# fancontroller.net
KiCad netlist of a schematic drawn in EAGLE
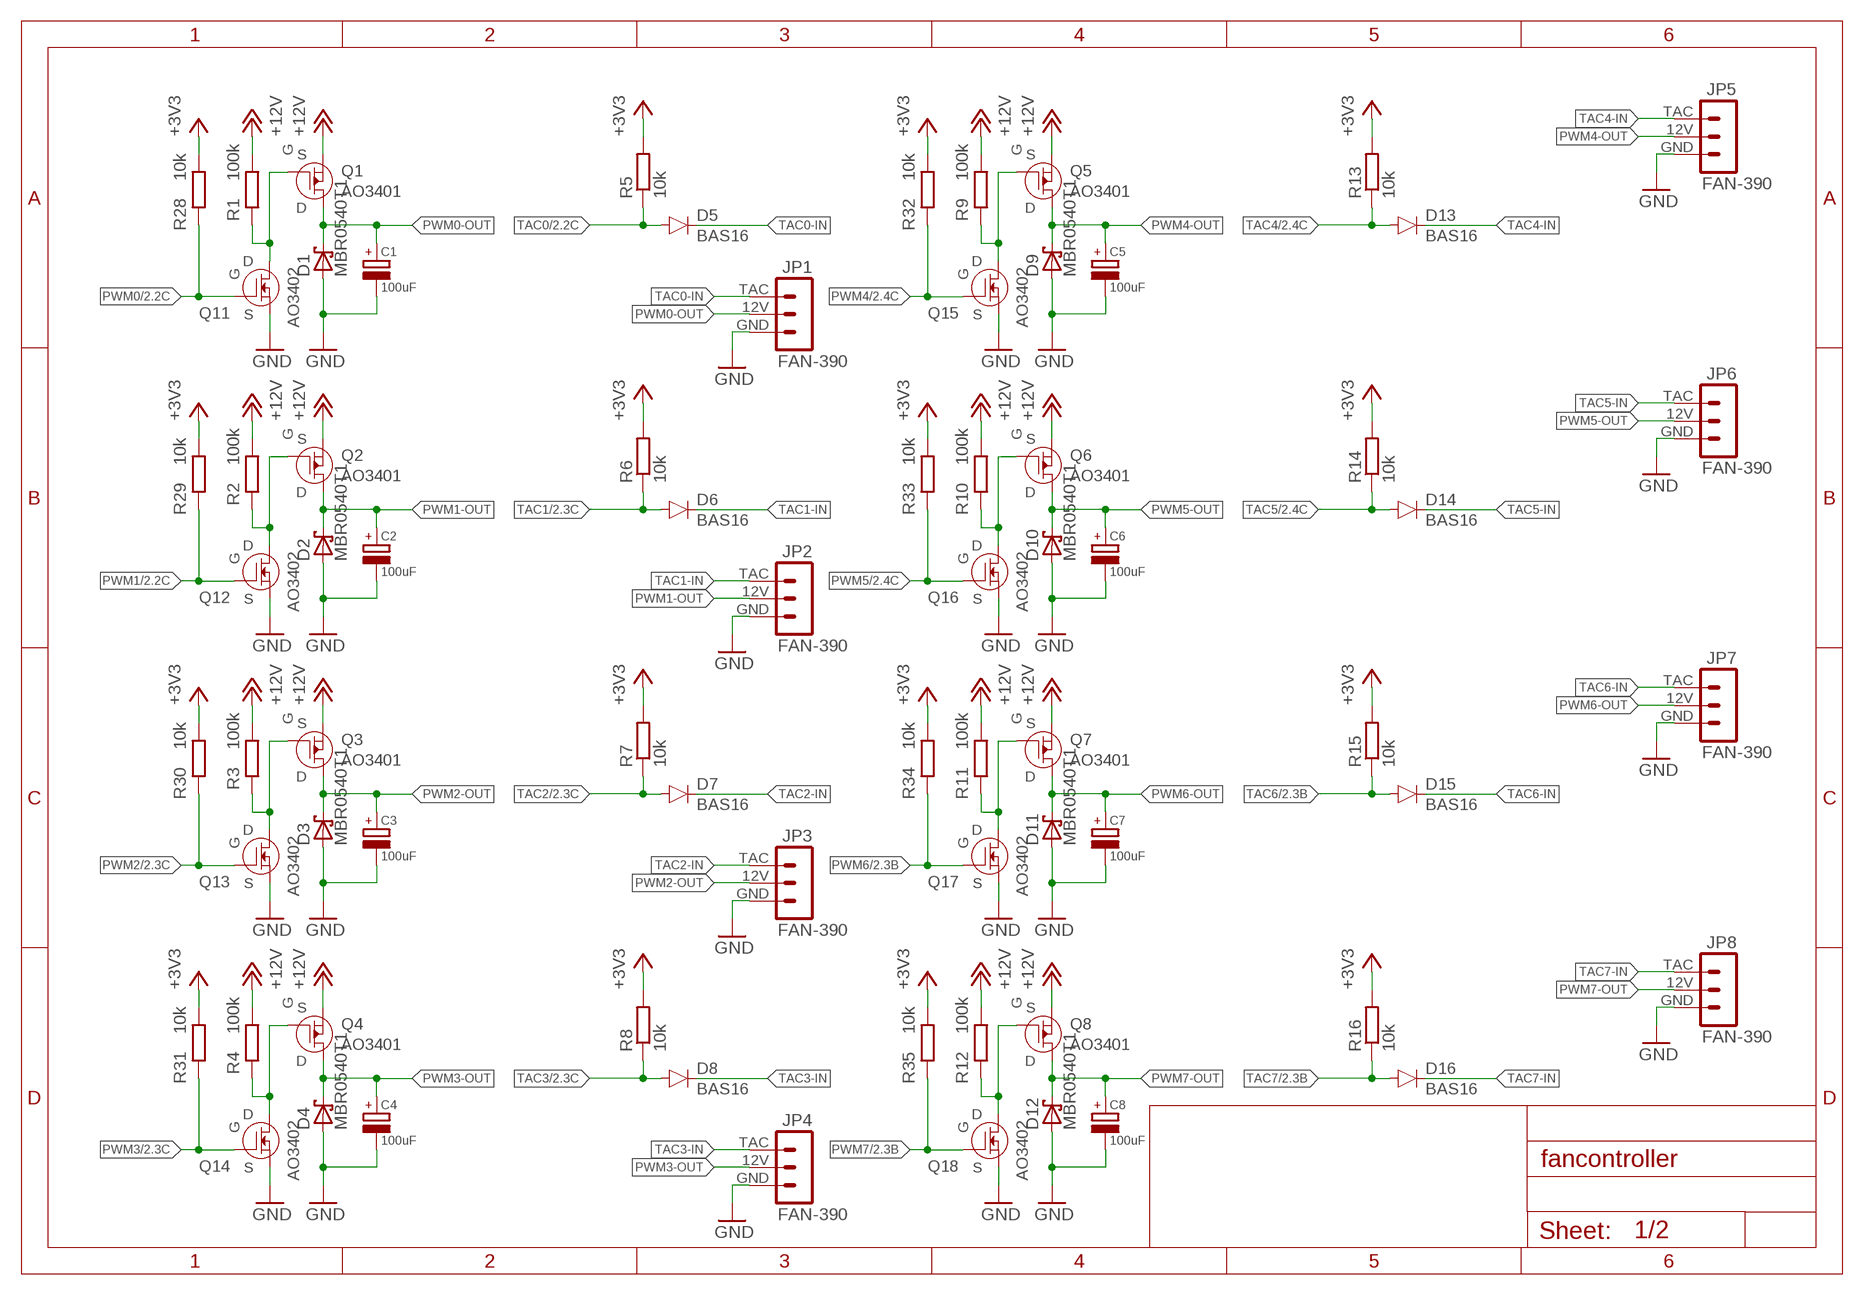
[diagram p0: schematic, sheet 1]
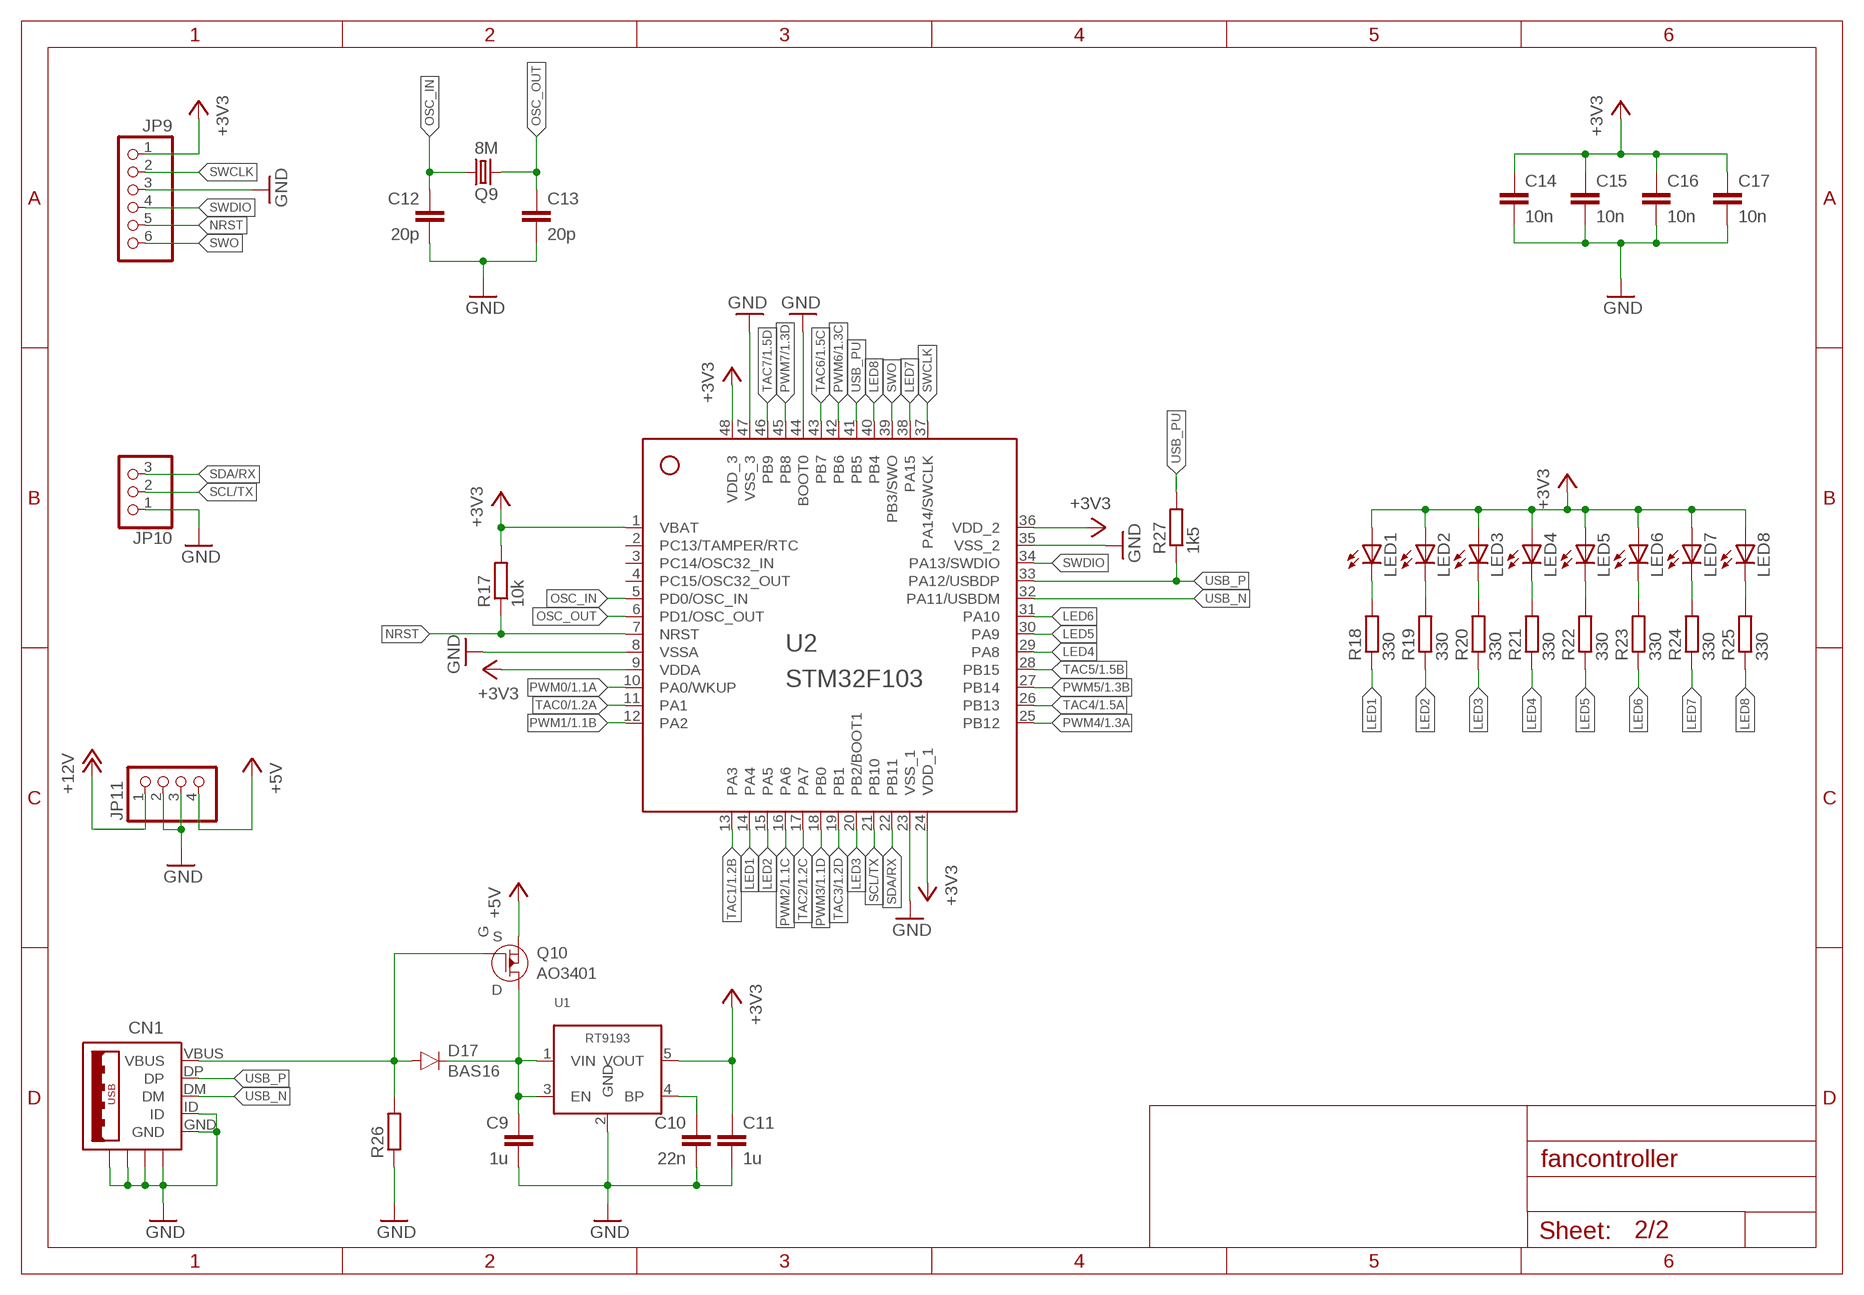
[diagram p1: schematic, sheet 2]

(export (version "E")
  (design (tool "Eeschema 10.0.6"))
  (components
    (comp (ref "C9")
      (value "1u")
      (footprint "eagle-import:0603")
      (libsource (lib "eagle-import") (part "C0603"))
    )
    (comp (ref "C10")
      (value "22n")
      (footprint "eagle-import:0603")
      (libsource (lib "eagle-import") (part "C0603"))
    )
    (comp (ref "C11")
      (value "1u")
      (footprint "eagle-import:0603")
      (libsource (lib "eagle-import") (part "C0603"))
    )
    (comp (ref "C12")
      (value "20p")
      (footprint "eagle-import:0603")
      (libsource (lib "eagle-import") (part "C0603"))
    )
    (comp (ref "C13")
      (value "20p")
      (footprint "eagle-import:0603")
      (libsource (lib "eagle-import") (part "C0603"))
    )
    (comp (ref "C14")
      (value "10n")
      (footprint "eagle-import:0603")
      (libsource (lib "eagle-import") (part "C0603"))
    )
    (comp (ref "C15")
      (value "10n")
      (footprint "eagle-import:0603")
      (libsource (lib "eagle-import") (part "C0603"))
    )
    (comp (ref "C16")
      (value "10n")
      (footprint "eagle-import:0603")
      (libsource (lib "eagle-import") (part "C0603"))
    )
    (comp (ref "C17")
      (value "10n")
      (footprint "eagle-import:0603")
      (libsource (lib "eagle-import") (part "C0603"))
    )
    (comp (ref "CN1")
      (value "USB-MICROB-2TABS")
      (footprint "eagle-import:USB-MICROB-2")
      (libsource (lib "eagle-import") (part "USB-MICROB-2TABS"))
    )
    (comp (ref "D17")
      (value "BAS16")
      (footprint "eagle-import:SOT23-3")
      (libsource (lib "eagle-import") (part "BAS16"))
    )
    (comp (ref "JP9")
      (value "PINHD-1X6")
      (footprint "eagle-import:1X06")
      (libsource (lib "eagle-import") (part "PINHD-1X6"))
    )
    (comp (ref "JP10")
      (value "PINHD-1X3/90")
      (footprint "eagle-import:1X03_90")
      (libsource (lib "eagle-import") (part "PINHD-1X3/90"))
    )
    (comp (ref "JP11")
      (value "PINHD-1X4/90")
      (footprint "eagle-import:1X04_90")
      (libsource (lib "eagle-import") (part "PINHD-1X4/90"))
    )
    (comp (ref "LED1")
      (value "LEDSML0805")
      (footprint "eagle-import:SML0805")
      (libsource (lib "eagle-import") (part "LEDSML0805"))
    )
    (comp (ref "LED2")
      (value "LEDSML0805")
      (footprint "eagle-import:SML0805")
      (libsource (lib "eagle-import") (part "LEDSML0805"))
    )
    (comp (ref "LED3")
      (value "LEDSML0805")
      (footprint "eagle-import:SML0805")
      (libsource (lib "eagle-import") (part "LEDSML0805"))
    )
    (comp (ref "LED4")
      (value "LEDSML0805")
      (footprint "eagle-import:SML0805")
      (libsource (lib "eagle-import") (part "LEDSML0805"))
    )
    (comp (ref "LED5")
      (value "LEDSML0805")
      (footprint "eagle-import:SML0805")
      (libsource (lib "eagle-import") (part "LEDSML0805"))
    )
    (comp (ref "LED6")
      (value "LEDSML0805")
      (footprint "eagle-import:SML0805")
      (libsource (lib "eagle-import") (part "LEDSML0805"))
    )
    (comp (ref "LED7")
      (value "LEDSML0805")
      (footprint "eagle-import:SML0805")
      (libsource (lib "eagle-import") (part "LEDSML0805"))
    )
    (comp (ref "LED8")
      (value "LEDSML0805")
      (footprint "eagle-import:SML0805")
      (libsource (lib "eagle-import") (part "LEDSML0805"))
    )
    (comp (ref "Q9")
      (value "8M")
      (footprint "eagle-import:HC49_S")
      (libsource (lib "eagle-import") (part "CRYSTALHC49S"))
    )
    (comp (ref "Q10")
      (value "AO3401")
      (footprint "eagle-import:SOT23-3")
      (libsource (lib "eagle-import") (part "AO3401"))
    )
    (comp (ref "R17")
      (value "10k")
      (footprint "eagle-import:R0603")
      (libsource (lib "eagle-import") (part "RR0603"))
    )
    (comp (ref "R18")
      (value "330")
      (footprint "eagle-import:R0603")
      (libsource (lib "eagle-import") (part "RR0603"))
    )
    (comp (ref "R19")
      (value "330")
      (footprint "eagle-import:R0603")
      (libsource (lib "eagle-import") (part "RR0603"))
    )
    (comp (ref "R20")
      (value "330")
      (footprint "eagle-import:R0603")
      (libsource (lib "eagle-import") (part "RR0603"))
    )
    (comp (ref "R21")
      (value "330")
      (footprint "eagle-import:R0603")
      (libsource (lib "eagle-import") (part "RR0603"))
    )
    (comp (ref "R22")
      (value "330")
      (footprint "eagle-import:R0603")
      (libsource (lib "eagle-import") (part "RR0603"))
    )
    (comp (ref "R23")
      (value "330")
      (footprint "eagle-import:R0603")
      (libsource (lib "eagle-import") (part "RR0603"))
    )
    (comp (ref "R24")
      (value "330")
      (footprint "eagle-import:R0603")
      (libsource (lib "eagle-import") (part "RR0603"))
    )
    (comp (ref "R25")
      (value "330")
      (footprint "eagle-import:R0603")
      (libsource (lib "eagle-import") (part "RR0603"))
    )
    (comp (ref "R26")
      (value "RR0603")
      (footprint "eagle-import:R0603")
      (libsource (lib "eagle-import") (part "RR0603"))
    )
    (comp (ref "R27")
      (value "1k5")
      (footprint "eagle-import:R0603")
      (libsource (lib "eagle-import") (part "RR0603"))
    )
    (comp (ref "U1")
      (value "RT9193")
      (footprint "eagle-import:SOT23-5")
      (libsource (lib "eagle-import") (part "RT9193"))
    )
    (comp (ref "U2")
      (value "STM32F103-48LQFP")
      (footprint "eagle-import:LQFP-48")
      (libsource (lib "eagle-import") (part "STM32F103-48LQFP"))
    )
    (comp (ref "C1")
      (value "100uF")
      (footprint "eagle-import:CAP-D6.3")
      (libsource (lib "eagle-import") (part "CAPACITOR"))
    )
    (comp (ref "C2")
      (value "100uF")
      (footprint "eagle-import:CAP-D6.3")
      (libsource (lib "eagle-import") (part "CAPACITOR"))
    )
    (comp (ref "C3")
      (value "100uF")
      (footprint "eagle-import:CAP-D6.3")
      (libsource (lib "eagle-import") (part "CAPACITOR"))
    )
    (comp (ref "C4")
      (value "100uF")
      (footprint "eagle-import:CAP-D6.3")
      (libsource (lib "eagle-import") (part "CAPACITOR"))
    )
    (comp (ref "C5")
      (value "100uF")
      (footprint "eagle-import:CAP-D6.3")
      (libsource (lib "eagle-import") (part "CAPACITOR"))
    )
    (comp (ref "C6")
      (value "100uF")
      (footprint "eagle-import:CAP-D6.3")
      (libsource (lib "eagle-import") (part "CAPACITOR"))
    )
    (comp (ref "C7")
      (value "100uF")
      (footprint "eagle-import:CAP-D6.3")
      (libsource (lib "eagle-import") (part "CAPACITOR"))
    )
    (comp (ref "C8")
      (value "100uF")
      (footprint "eagle-import:CAP-D6.3")
      (libsource (lib "eagle-import") (part "CAPACITOR"))
    )
    (comp (ref "D1")
      (value "MBR0540T1")
      (footprint "eagle-import:SOD123")
      (libsource (lib "eagle-import") (part "MBR0540T1"))
    )
    (comp (ref "D2")
      (value "MBR0540T1")
      (footprint "eagle-import:SOD123")
      (libsource (lib "eagle-import") (part "MBR0540T1"))
    )
    (comp (ref "D3")
      (value "MBR0540T1")
      (footprint "eagle-import:SOD123")
      (libsource (lib "eagle-import") (part "MBR0540T1"))
    )
    (comp (ref "D4")
      (value "MBR0540T1")
      (footprint "eagle-import:SOD123")
      (libsource (lib "eagle-import") (part "MBR0540T1"))
    )
    (comp (ref "D5")
      (value "BAS16")
      (footprint "eagle-import:SOT23-3")
      (libsource (lib "eagle-import") (part "BAS16"))
    )
    (comp (ref "D6")
      (value "BAS16")
      (footprint "eagle-import:SOT23-3")
      (libsource (lib "eagle-import") (part "BAS16"))
    )
    (comp (ref "D7")
      (value "BAS16")
      (footprint "eagle-import:SOT23-3")
      (libsource (lib "eagle-import") (part "BAS16"))
    )
    (comp (ref "D8")
      (value "BAS16")
      (footprint "eagle-import:SOT23-3")
      (libsource (lib "eagle-import") (part "BAS16"))
    )
    (comp (ref "D9")
      (value "MBR0540T1")
      (footprint "eagle-import:SOD123")
      (libsource (lib "eagle-import") (part "MBR0540T1"))
    )
    (comp (ref "D10")
      (value "MBR0540T1")
      (footprint "eagle-import:SOD123")
      (libsource (lib "eagle-import") (part "MBR0540T1"))
    )
    (comp (ref "D11")
      (value "MBR0540T1")
      (footprint "eagle-import:SOD123")
      (libsource (lib "eagle-import") (part "MBR0540T1"))
    )
    (comp (ref "D12")
      (value "MBR0540T1")
      (footprint "eagle-import:SOD123")
      (libsource (lib "eagle-import") (part "MBR0540T1"))
    )
    (comp (ref "D13")
      (value "BAS16")
      (footprint "eagle-import:SOT23-3")
      (libsource (lib "eagle-import") (part "BAS16"))
    )
    (comp (ref "D14")
      (value "BAS16")
      (footprint "eagle-import:SOT23-3")
      (libsource (lib "eagle-import") (part "BAS16"))
    )
    (comp (ref "D15")
      (value "BAS16")
      (footprint "eagle-import:SOT23-3")
      (libsource (lib "eagle-import") (part "BAS16"))
    )
    (comp (ref "D16")
      (value "BAS16")
      (footprint "eagle-import:SOT23-3")
      (libsource (lib "eagle-import") (part "BAS16"))
    )
    (comp (ref "JP1")
      (value "FAN-390")
      (footprint "eagle-import:FAN-3PIN_90")
      (libsource (lib "eagle-import") (part "FAN-390"))
    )
    (comp (ref "JP2")
      (value "FAN-390")
      (footprint "eagle-import:FAN-3PIN_90")
      (libsource (lib "eagle-import") (part "FAN-390"))
    )
    (comp (ref "JP3")
      (value "FAN-390")
      (footprint "eagle-import:FAN-3PIN_90")
      (libsource (lib "eagle-import") (part "FAN-390"))
    )
    (comp (ref "JP4")
      (value "FAN-390")
      (footprint "eagle-import:FAN-3PIN_90")
      (libsource (lib "eagle-import") (part "FAN-390"))
    )
    (comp (ref "JP5")
      (value "FAN-390")
      (footprint "eagle-import:FAN-3PIN_90")
      (libsource (lib "eagle-import") (part "FAN-390"))
    )
    (comp (ref "JP6")
      (value "FAN-390")
      (footprint "eagle-import:FAN-3PIN_90")
      (libsource (lib "eagle-import") (part "FAN-390"))
    )
    (comp (ref "JP7")
      (value "FAN-390")
      (footprint "eagle-import:FAN-3PIN_90")
      (libsource (lib "eagle-import") (part "FAN-390"))
    )
    (comp (ref "JP8")
      (value "FAN-390")
      (footprint "eagle-import:FAN-3PIN_90")
      (libsource (lib "eagle-import") (part "FAN-390"))
    )
    (comp (ref "Q1")
      (value "AO3401")
      (footprint "eagle-import:SOT23-3")
      (libsource (lib "eagle-import") (part "AO3401"))
    )
    (comp (ref "Q2")
      (value "AO3401")
      (footprint "eagle-import:SOT23-3")
      (libsource (lib "eagle-import") (part "AO3401"))
    )
    (comp (ref "Q3")
      (value "AO3401")
      (footprint "eagle-import:SOT23-3")
      (libsource (lib "eagle-import") (part "AO3401"))
    )
    (comp (ref "Q4")
      (value "AO3401")
      (footprint "eagle-import:SOT23-3")
      (libsource (lib "eagle-import") (part "AO3401"))
    )
    (comp (ref "Q5")
      (value "AO3401")
      (footprint "eagle-import:SOT23-3")
      (libsource (lib "eagle-import") (part "AO3401"))
    )
    (comp (ref "Q6")
      (value "AO3401")
      (footprint "eagle-import:SOT23-3")
      (libsource (lib "eagle-import") (part "AO3401"))
    )
    (comp (ref "Q7")
      (value "AO3401")
      (footprint "eagle-import:SOT23-3")
      (libsource (lib "eagle-import") (part "AO3401"))
    )
    (comp (ref "Q8")
      (value "AO3401")
      (footprint "eagle-import:SOT23-3")
      (libsource (lib "eagle-import") (part "AO3401"))
    )
    (comp (ref "Q11")
      (value "AO3402")
      (footprint "eagle-import:SOT23-3")
      (libsource (lib "eagle-import") (part "AO3402"))
    )
    (comp (ref "Q12")
      (value "AO3402")
      (footprint "eagle-import:SOT23-3")
      (libsource (lib "eagle-import") (part "AO3402"))
    )
    (comp (ref "Q13")
      (value "AO3402")
      (footprint "eagle-import:SOT23-3")
      (libsource (lib "eagle-import") (part "AO3402"))
    )
    (comp (ref "Q14")
      (value "AO3402")
      (footprint "eagle-import:SOT23-3")
      (libsource (lib "eagle-import") (part "AO3402"))
    )
    (comp (ref "Q15")
      (value "AO3402")
      (footprint "eagle-import:SOT23-3")
      (libsource (lib "eagle-import") (part "AO3402"))
    )
    (comp (ref "Q16")
      (value "AO3402")
      (footprint "eagle-import:SOT23-3")
      (libsource (lib "eagle-import") (part "AO3402"))
    )
    (comp (ref "Q17")
      (value "AO3402")
      (footprint "eagle-import:SOT23-3")
      (libsource (lib "eagle-import") (part "AO3402"))
    )
    (comp (ref "Q18")
      (value "AO3402")
      (footprint "eagle-import:SOT23-3")
      (libsource (lib "eagle-import") (part "AO3402"))
    )
    (comp (ref "R1")
      (value "100k")
      (footprint "eagle-import:R0603")
      (libsource (lib "eagle-import") (part "RR0603"))
    )
    (comp (ref "R2")
      (value "100k")
      (footprint "eagle-import:R0603")
      (libsource (lib "eagle-import") (part "RR0603"))
    )
    (comp (ref "R3")
      (value "100k")
      (footprint "eagle-import:R0603")
      (libsource (lib "eagle-import") (part "RR0603"))
    )
    (comp (ref "R4")
      (value "100k")
      (footprint "eagle-import:R0603")
      (libsource (lib "eagle-import") (part "RR0603"))
    )
    (comp (ref "R5")
      (value "10k")
      (footprint "eagle-import:R0603")
      (libsource (lib "eagle-import") (part "RR0603"))
    )
    (comp (ref "R6")
      (value "10k")
      (footprint "eagle-import:R0603")
      (libsource (lib "eagle-import") (part "RR0603"))
    )
    (comp (ref "R7")
      (value "10k")
      (footprint "eagle-import:R0603")
      (libsource (lib "eagle-import") (part "RR0603"))
    )
    (comp (ref "R8")
      (value "10k")
      (footprint "eagle-import:R0603")
      (libsource (lib "eagle-import") (part "RR0603"))
    )
    (comp (ref "R9")
      (value "100k")
      (footprint "eagle-import:R0603")
      (libsource (lib "eagle-import") (part "RR0603"))
    )
    (comp (ref "R10")
      (value "100k")
      (footprint "eagle-import:R0603")
      (libsource (lib "eagle-import") (part "RR0603"))
    )
    (comp (ref "R11")
      (value "100k")
      (footprint "eagle-import:R0603")
      (libsource (lib "eagle-import") (part "RR0603"))
    )
    (comp (ref "R12")
      (value "100k")
      (footprint "eagle-import:R0603")
      (libsource (lib "eagle-import") (part "RR0603"))
    )
    (comp (ref "R13")
      (value "10k")
      (footprint "eagle-import:R0603")
      (libsource (lib "eagle-import") (part "RR0603"))
    )
    (comp (ref "R14")
      (value "10k")
      (footprint "eagle-import:R0603")
      (libsource (lib "eagle-import") (part "RR0603"))
    )
    (comp (ref "R15")
      (value "10k")
      (footprint "eagle-import:R0603")
      (libsource (lib "eagle-import") (part "RR0603"))
    )
    (comp (ref "R16")
      (value "10k")
      (footprint "eagle-import:R0603")
      (libsource (lib "eagle-import") (part "RR0603"))
    )
    (comp (ref "R28")
      (value "10k")
      (footprint "eagle-import:R0603")
      (libsource (lib "eagle-import") (part "RR0603"))
    )
    (comp (ref "R29")
      (value "10k")
      (footprint "eagle-import:R0603")
      (libsource (lib "eagle-import") (part "RR0603"))
    )
    (comp (ref "R30")
      (value "10k")
      (footprint "eagle-import:R0603")
      (libsource (lib "eagle-import") (part "RR0603"))
    )
    (comp (ref "R31")
      (value "10k")
      (footprint "eagle-import:R0603")
      (libsource (lib "eagle-import") (part "RR0603"))
    )
    (comp (ref "R32")
      (value "10k")
      (footprint "eagle-import:R0603")
      (libsource (lib "eagle-import") (part "RR0603"))
    )
    (comp (ref "R33")
      (value "10k")
      (footprint "eagle-import:R0603")
      (libsource (lib "eagle-import") (part "RR0603"))
    )
    (comp (ref "R34")
      (value "10k")
      (footprint "eagle-import:R0603")
      (libsource (lib "eagle-import") (part "RR0603"))
    )
    (comp (ref "R35")
      (value "10k")
      (footprint "eagle-import:R0603")
      (libsource (lib "eagle-import") (part "RR0603"))
    )
  )
  (nets
    (net (code "1") (name "+3V3") (class "Default")
      (node (ref "C11") (pin "1") (pinfunction "1_1") (pintype "passive"))
      (node (ref "C14") (pin "1") (pinfunction "1_1") (pintype "passive"))
      (node (ref "C15") (pin "1") (pinfunction "1_1") (pintype "passive"))
      (node (ref "C16") (pin "1") (pinfunction "1_1") (pintype "passive"))
      (node (ref "C17") (pin "1") (pinfunction "1_1") (pintype "passive"))
      (node (ref "JP9") (pin "1") (pinfunction "1_1") (pintype "passive"))
      (node (ref "LED1") (pin "A") (pinfunction "A_A") (pintype "passive"))
      (node (ref "LED2") (pin "A") (pinfunction "A_A") (pintype "passive"))
      (node (ref "LED3") (pin "A") (pinfunction "A_A") (pintype "passive"))
      (node (ref "LED4") (pin "A") (pinfunction "A_A") (pintype "passive"))
      (node (ref "LED5") (pin "A") (pinfunction "A_A") (pintype "passive"))
      (node (ref "LED6") (pin "A") (pinfunction "A_A") (pintype "passive"))
      (node (ref "LED7") (pin "A") (pinfunction "A_A") (pintype "passive"))
      (node (ref "LED8") (pin "A") (pinfunction "A_A") (pintype "passive"))
      (node (ref "R13") (pin "2") (pinfunction "2_2") (pintype "passive"))
      (node (ref "R14") (pin "2") (pinfunction "2_2") (pintype "passive"))
      (node (ref "R15") (pin "2") (pinfunction "2_2") (pintype "passive"))
      (node (ref "R16") (pin "2") (pinfunction "2_2") (pintype "passive"))
      (node (ref "R17") (pin "2") (pinfunction "2_2") (pintype "passive"))
      (node (ref "R28") (pin "2") (pinfunction "2_2") (pintype "passive"))
      (node (ref "R29") (pin "2") (pinfunction "2_2") (pintype "passive"))
      (node (ref "R30") (pin "2") (pinfunction "2_2") (pintype "passive"))
      (node (ref "R31") (pin "2") (pinfunction "2_2") (pintype "passive"))
      (node (ref "R32") (pin "2") (pinfunction "2_2") (pintype "passive"))
      (node (ref "R33") (pin "2") (pinfunction "2_2") (pintype "passive"))
      (node (ref "R34") (pin "2") (pinfunction "2_2") (pintype "passive"))
      (node (ref "R35") (pin "2") (pinfunction "2_2") (pintype "passive"))
      (node (ref "R5") (pin "2") (pinfunction "2_2") (pintype "passive"))
      (node (ref "R6") (pin "2") (pinfunction "2_2") (pintype "passive"))
      (node (ref "R7") (pin "2") (pinfunction "2_2") (pintype "passive"))
      (node (ref "R8") (pin "2") (pinfunction "2_2") (pintype "passive"))
      (node (ref "U1") (pin "5") (pinfunction "VOUT_5") (pintype "bidirectional"))
      (node (ref "U2") (pin "1") (pinfunction "VBAT_1") (pintype "bidirectional"))
      (node (ref "U2") (pin "24") (pinfunction "VDD_1_24") (pintype "bidirectional"))
      (node (ref "U2") (pin "36") (pinfunction "VDD_2_36") (pintype "bidirectional"))
      (node (ref "U2") (pin "48") (pinfunction "VDD_3_48") (pintype "bidirectional"))
      (node (ref "U2") (pin "9") (pinfunction "VDDA_9") (pintype "bidirectional"))
    )
    (net (code "2") (name "+5V") (class "Default")
      (node (ref "JP11") (pin "4") (pinfunction "4_4") (pintype "passive"))
      (node (ref "Q10") (pin "2") (pinfunction "S_2") (pintype "bidirectional"))
    )
    (net (code "3") (name "+12V") (class "Default")
      (node (ref "JP11") (pin "1") (pinfunction "1_1") (pintype "passive"))
      (node (ref "Q1") (pin "2") (pinfunction "S_2") (pintype "bidirectional"))
      (node (ref "Q2") (pin "2") (pinfunction "S_2") (pintype "bidirectional"))
      (node (ref "Q3") (pin "2") (pinfunction "S_2") (pintype "bidirectional"))
      (node (ref "Q4") (pin "2") (pinfunction "S_2") (pintype "bidirectional"))
      (node (ref "Q5") (pin "2") (pinfunction "S_2") (pintype "bidirectional"))
      (node (ref "Q6") (pin "2") (pinfunction "S_2") (pintype "bidirectional"))
      (node (ref "Q7") (pin "2") (pinfunction "S_2") (pintype "bidirectional"))
      (node (ref "Q8") (pin "2") (pinfunction "S_2") (pintype "bidirectional"))
      (node (ref "R1") (pin "2") (pinfunction "2_2") (pintype "passive"))
      (node (ref "R10") (pin "2") (pinfunction "2_2") (pintype "passive"))
      (node (ref "R11") (pin "2") (pinfunction "2_2") (pintype "passive"))
      (node (ref "R12") (pin "2") (pinfunction "2_2") (pintype "passive"))
      (node (ref "R2") (pin "2") (pinfunction "2_2") (pintype "passive"))
      (node (ref "R3") (pin "2") (pinfunction "2_2") (pintype "passive"))
      (node (ref "R4") (pin "2") (pinfunction "2_2") (pintype "passive"))
      (node (ref "R9") (pin "2") (pinfunction "2_2") (pintype "passive"))
    )
    (net (code "4") (name "GND") (class "Default")
      (node (ref "C1") (pin "N") (pinfunction "NEG_N") (pintype "passive"))
      (node (ref "C10") (pin "2") (pinfunction "2_2") (pintype "passive"))
      (node (ref "C11") (pin "2") (pinfunction "2_2") (pintype "passive"))
      (node (ref "C12") (pin "2") (pinfunction "2_2") (pintype "passive"))
      (node (ref "C13") (pin "2") (pinfunction "2_2") (pintype "passive"))
      (node (ref "C14") (pin "2") (pinfunction "2_2") (pintype "passive"))
      (node (ref "C15") (pin "2") (pinfunction "2_2") (pintype "passive"))
      (node (ref "C16") (pin "2") (pinfunction "2_2") (pintype "passive"))
      (node (ref "C17") (pin "2") (pinfunction "2_2") (pintype "passive"))
      (node (ref "C2") (pin "N") (pinfunction "NEG_N") (pintype "passive"))
      (node (ref "C3") (pin "N") (pinfunction "NEG_N") (pintype "passive"))
      (node (ref "C4") (pin "N") (pinfunction "NEG_N") (pintype "passive"))
      (node (ref "C5") (pin "N") (pinfunction "NEG_N") (pintype "passive"))
      (node (ref "C6") (pin "N") (pinfunction "NEG_N") (pintype "passive"))
      (node (ref "C7") (pin "N") (pinfunction "NEG_N") (pintype "passive"))
      (node (ref "C8") (pin "N") (pinfunction "NEG_N") (pintype "passive"))
      (node (ref "C9") (pin "2") (pinfunction "2_2") (pintype "passive"))
      (node (ref "CN1") (pin "GND") (pinfunction "GND_GND") (pintype "passive"))
      (node (ref "CN1") (pin "GND@1") (pinfunction "GND_GND@1") (pintype "power_in"))
      (node (ref "CN1") (pin "GND@2") (pinfunction "GND_GND@2") (pintype "power_in"))
      (node (ref "CN1") (pin "GND@3") (pinfunction "GND_GND@3") (pintype "power_in"))
      (node (ref "CN1") (pin "GND@4") (pinfunction "GND_GND@4") (pintype "power_in"))
      (node (ref "CN1") (pin "ID") (pinfunction "ID_ID") (pintype "passive"))
      (node (ref "D1") (pin "A") (pinfunction "A_A") (pintype "passive"))
      (node (ref "D10") (pin "A") (pinfunction "A_A") (pintype "passive"))
      (node (ref "D11") (pin "A") (pinfunction "A_A") (pintype "passive"))
      (node (ref "D12") (pin "A") (pinfunction "A_A") (pintype "passive"))
      (node (ref "D2") (pin "A") (pinfunction "A_A") (pintype "passive"))
      (node (ref "D3") (pin "A") (pinfunction "A_A") (pintype "passive"))
      (node (ref "D4") (pin "A") (pinfunction "A_A") (pintype "passive"))
      (node (ref "D9") (pin "A") (pinfunction "A_A") (pintype "passive"))
      (node (ref "JP1") (pin "GND") (pinfunction "1_GND") (pintype "passive"))
      (node (ref "JP10") (pin "1") (pinfunction "1_1") (pintype "passive"))
      (node (ref "JP11") (pin "2") (pinfunction "2_2") (pintype "passive"))
      (node (ref "JP11") (pin "3") (pinfunction "3_3") (pintype "passive"))
      (node (ref "JP2") (pin "GND") (pinfunction "1_GND") (pintype "passive"))
      (node (ref "JP3") (pin "GND") (pinfunction "1_GND") (pintype "passive"))
      (node (ref "JP4") (pin "GND") (pinfunction "1_GND") (pintype "passive"))
      (node (ref "JP5") (pin "GND") (pinfunction "1_GND") (pintype "passive"))
      (node (ref "JP6") (pin "GND") (pinfunction "1_GND") (pintype "passive"))
      (node (ref "JP7") (pin "GND") (pinfunction "1_GND") (pintype "passive"))
      (node (ref "JP8") (pin "GND") (pinfunction "1_GND") (pintype "passive"))
      (node (ref "JP9") (pin "3") (pinfunction "3_3") (pintype "passive"))
      (node (ref "Q11") (pin "2") (pinfunction "S_2") (pintype "bidirectional"))
      (node (ref "Q12") (pin "2") (pinfunction "S_2") (pintype "bidirectional"))
      (node (ref "Q13") (pin "2") (pinfunction "S_2") (pintype "bidirectional"))
      (node (ref "Q14") (pin "2") (pinfunction "S_2") (pintype "bidirectional"))
      (node (ref "Q15") (pin "2") (pinfunction "S_2") (pintype "bidirectional"))
      (node (ref "Q16") (pin "2") (pinfunction "S_2") (pintype "bidirectional"))
      (node (ref "Q17") (pin "2") (pinfunction "S_2") (pintype "bidirectional"))
      (node (ref "Q18") (pin "2") (pinfunction "S_2") (pintype "bidirectional"))
      (node (ref "R26") (pin "1") (pinfunction "1_1") (pintype "passive"))
      (node (ref "U1") (pin "2") (pinfunction "GND_2") (pintype "bidirectional"))
      (node (ref "U2") (pin "23") (pinfunction "VSS_1_23") (pintype "bidirectional"))
      (node (ref "U2") (pin "35") (pinfunction "VSS_2_35") (pintype "bidirectional"))
      (node (ref "U2") (pin "44") (pinfunction "BOOT0_44") (pintype "bidirectional"))
      (node (ref "U2") (pin "47") (pinfunction "VSS_3_47") (pintype "bidirectional"))
      (node (ref "U2") (pin "8") (pinfunction "VSSA_8") (pintype "bidirectional"))
    )
    (net (code "5") (name "LED1") (class "Default")
      (node (ref "R18") (pin "1") (pinfunction "1_1") (pintype "passive"))
      (node (ref "U2") (pin "14") (pinfunction "PA4_14") (pintype "bidirectional"))
    )
    (net (code "6") (name "LED2") (class "Default")
      (node (ref "R19") (pin "1") (pinfunction "1_1") (pintype "passive"))
      (node (ref "U2") (pin "15") (pinfunction "PA5_15") (pintype "bidirectional"))
    )
    (net (code "7") (name "LED3") (class "Default")
      (node (ref "R20") (pin "1") (pinfunction "1_1") (pintype "passive"))
      (node (ref "U2") (pin "20") (pinfunction "PB2/BOOT1_20") (pintype "bidirectional"))
    )
    (net (code "8") (name "LED4") (class "Default")
      (node (ref "R21") (pin "1") (pinfunction "1_1") (pintype "passive"))
      (node (ref "U2") (pin "29") (pinfunction "PA8_29") (pintype "bidirectional"))
    )
    (net (code "9") (name "LED5") (class "Default")
      (node (ref "R22") (pin "1") (pinfunction "1_1") (pintype "passive"))
      (node (ref "U2") (pin "30") (pinfunction "PA9_30") (pintype "bidirectional"))
    )
    (net (code "10") (name "LED6") (class "Default")
      (node (ref "R23") (pin "1") (pinfunction "1_1") (pintype "passive"))
      (node (ref "U2") (pin "31") (pinfunction "PA10_31") (pintype "bidirectional"))
    )
    (net (code "11") (name "LED7") (class "Default")
      (node (ref "R24") (pin "1") (pinfunction "1_1") (pintype "passive"))
      (node (ref "U2") (pin "38") (pinfunction "PA15_38") (pintype "bidirectional"))
    )
    (net (code "12") (name "LED8") (class "Default")
      (node (ref "R25") (pin "1") (pinfunction "1_1") (pintype "passive"))
      (node (ref "U2") (pin "40") (pinfunction "PB4_40") (pintype "bidirectional"))
    )
    (net (code "13") (name "NRST") (class "Default")
      (node (ref "JP9") (pin "5") (pinfunction "5_5") (pintype "passive"))
      (node (ref "R17") (pin "1") (pinfunction "1_1") (pintype "passive"))
      (node (ref "U2") (pin "7") (pinfunction "NRST_7") (pintype "bidirectional"))
    )
    (net (code "14") (name "Net-(D17-A)") (class "Default")
      (node (ref "CN1") (pin "VBUS") (pinfunction "VBUS_VBUS") (pintype "passive"))
      (node (ref "D17") (pin "1") (pinfunction "A_1") (pintype "bidirectional"))
      (node (ref "Q10") (pin "1") (pinfunction "G_1") (pintype "bidirectional"))
      (node (ref "R26") (pin "2") (pinfunction "2_2") (pintype "passive"))
    )
    (net (code "15") (name "Net-(D17-C)") (class "Default")
      (node (ref "C9") (pin "1") (pinfunction "1_1") (pintype "passive"))
      (node (ref "D17") (pin "3") (pinfunction "C_3") (pintype "bidirectional"))
      (node (ref "Q10") (pin "3") (pinfunction "D_3") (pintype "bidirectional"))
      (node (ref "U1") (pin "1") (pinfunction "VIN_1") (pintype "bidirectional"))
      (node (ref "U1") (pin "3") (pinfunction "EN_3") (pintype "bidirectional"))
    )
    (net (code "16") (name "Net-(LED1-PadC)") (class "Default")
      (node (ref "LED1") (pin "C") (pinfunction "C_C") (pintype "passive"))
      (node (ref "R18") (pin "2") (pinfunction "2_2") (pintype "passive"))
    )
    (net (code "17") (name "Net-(LED2-PadC)") (class "Default")
      (node (ref "LED2") (pin "C") (pinfunction "C_C") (pintype "passive"))
      (node (ref "R19") (pin "2") (pinfunction "2_2") (pintype "passive"))
    )
    (net (code "18") (name "Net-(LED3-PadC)") (class "Default")
      (node (ref "LED3") (pin "C") (pinfunction "C_C") (pintype "passive"))
      (node (ref "R20") (pin "2") (pinfunction "2_2") (pintype "passive"))
    )
    (net (code "19") (name "Net-(LED4-PadC)") (class "Default")
      (node (ref "LED4") (pin "C") (pinfunction "C_C") (pintype "passive"))
      (node (ref "R21") (pin "2") (pinfunction "2_2") (pintype "passive"))
    )
    (net (code "20") (name "Net-(LED5-PadC)") (class "Default")
      (node (ref "LED5") (pin "C") (pinfunction "C_C") (pintype "passive"))
      (node (ref "R22") (pin "2") (pinfunction "2_2") (pintype "passive"))
    )
    (net (code "21") (name "Net-(LED6-PadC)") (class "Default")
      (node (ref "LED6") (pin "C") (pinfunction "C_C") (pintype "passive"))
      (node (ref "R23") (pin "2") (pinfunction "2_2") (pintype "passive"))
    )
    (net (code "22") (name "Net-(LED7-PadC)") (class "Default")
      (node (ref "LED7") (pin "C") (pinfunction "C_C") (pintype "passive"))
      (node (ref "R24") (pin "2") (pinfunction "2_2") (pintype "passive"))
    )
    (net (code "23") (name "Net-(LED8-PadC)") (class "Default")
      (node (ref "LED8") (pin "C") (pinfunction "C_C") (pintype "passive"))
      (node (ref "R25") (pin "2") (pinfunction "2_2") (pintype "passive"))
    )
    (net (code "24") (name "Net-(Q1-G)") (class "Default")
      (node (ref "Q1") (pin "1") (pinfunction "G_1") (pintype "bidirectional"))
      (node (ref "Q11") (pin "3") (pinfunction "D_3") (pintype "bidirectional"))
      (node (ref "R1") (pin "1") (pinfunction "1_1") (pintype "passive"))
    )
    (net (code "25") (name "Net-(Q12-D)") (class "Default")
      (node (ref "Q12") (pin "3") (pinfunction "D_3") (pintype "bidirectional"))
      (node (ref "Q2") (pin "1") (pinfunction "G_1") (pintype "bidirectional"))
      (node (ref "R2") (pin "1") (pinfunction "1_1") (pintype "passive"))
    )
    (net (code "26") (name "Net-(Q13-D)") (class "Default")
      (node (ref "Q13") (pin "3") (pinfunction "D_3") (pintype "bidirectional"))
      (node (ref "Q3") (pin "1") (pinfunction "G_1") (pintype "bidirectional"))
      (node (ref "R3") (pin "1") (pinfunction "1_1") (pintype "passive"))
    )
    (net (code "27") (name "Net-(Q14-D)") (class "Default")
      (node (ref "Q14") (pin "3") (pinfunction "D_3") (pintype "bidirectional"))
      (node (ref "Q4") (pin "1") (pinfunction "G_1") (pintype "bidirectional"))
      (node (ref "R4") (pin "1") (pinfunction "1_1") (pintype "passive"))
    )
    (net (code "28") (name "Net-(Q15-D)") (class "Default")
      (node (ref "Q15") (pin "3") (pinfunction "D_3") (pintype "bidirectional"))
      (node (ref "Q5") (pin "1") (pinfunction "G_1") (pintype "bidirectional"))
      (node (ref "R9") (pin "1") (pinfunction "1_1") (pintype "passive"))
    )
    (net (code "29") (name "Net-(Q16-D)") (class "Default")
      (node (ref "Q16") (pin "3") (pinfunction "D_3") (pintype "bidirectional"))
      (node (ref "Q6") (pin "1") (pinfunction "G_1") (pintype "bidirectional"))
      (node (ref "R10") (pin "1") (pinfunction "1_1") (pintype "passive"))
    )
    (net (code "30") (name "Net-(Q17-D)") (class "Default")
      (node (ref "Q17") (pin "3") (pinfunction "D_3") (pintype "bidirectional"))
      (node (ref "Q7") (pin "1") (pinfunction "G_1") (pintype "bidirectional"))
      (node (ref "R11") (pin "1") (pinfunction "1_1") (pintype "passive"))
    )
    (net (code "31") (name "Net-(Q18-D)") (class "Default")
      (node (ref "Q18") (pin "3") (pinfunction "D_3") (pintype "bidirectional"))
      (node (ref "Q8") (pin "1") (pinfunction "G_1") (pintype "bidirectional"))
      (node (ref "R12") (pin "1") (pinfunction "1_1") (pintype "passive"))
    )
    (net (code "32") (name "Net-(U1-BP)") (class "Default")
      (node (ref "C10") (pin "1") (pinfunction "1_1") (pintype "passive"))
      (node (ref "U1") (pin "4") (pinfunction "BP_4") (pintype "bidirectional"))
    )
    (net (code "33") (name "OSC_IN") (class "Default")
      (node (ref "C12") (pin "1") (pinfunction "1_1") (pintype "passive"))
      (node (ref "Q9") (pin "1") (pinfunction "1_1") (pintype "passive"))
      (node (ref "U2") (pin "5") (pinfunction "PD0/OSC_IN_5") (pintype "bidirectional"))
    )
    (net (code "34") (name "OSC_OUT") (class "Default")
      (node (ref "C13") (pin "1") (pinfunction "1_1") (pintype "passive"))
      (node (ref "Q9") (pin "2") (pinfunction "2_2") (pintype "passive"))
      (node (ref "U2") (pin "6") (pinfunction "PD1/OSC_OUT_6") (pintype "bidirectional"))
    )
    (net (code "35") (name "PWM0") (class "Default")
      (node (ref "Q11") (pin "1") (pinfunction "G_1") (pintype "bidirectional"))
      (node (ref "R28") (pin "1") (pinfunction "1_1") (pintype "passive"))
      (node (ref "U2") (pin "10") (pinfunction "PA0/WKUP_10") (pintype "bidirectional"))
    )
    (net (code "36") (name "PWM0-OUT") (class "Default")
      (node (ref "C1") (pin "P") (pinfunction "POS_P") (pintype "passive"))
      (node (ref "D1") (pin "C") (pinfunction "C_C") (pintype "passive"))
      (node (ref "JP1") (pin "12V") (pinfunction "2_12V") (pintype "passive"))
      (node (ref "Q1") (pin "3") (pinfunction "D_3") (pintype "bidirectional"))
    )
    (net (code "37") (name "PWM1") (class "Default")
      (node (ref "Q12") (pin "1") (pinfunction "G_1") (pintype "bidirectional"))
      (node (ref "R29") (pin "1") (pinfunction "1_1") (pintype "passive"))
      (node (ref "U2") (pin "12") (pinfunction "PA2_12") (pintype "bidirectional"))
    )
    (net (code "38") (name "PWM1-OUT") (class "Default")
      (node (ref "C2") (pin "P") (pinfunction "POS_P") (pintype "passive"))
      (node (ref "D2") (pin "C") (pinfunction "C_C") (pintype "passive"))
      (node (ref "JP2") (pin "12V") (pinfunction "2_12V") (pintype "passive"))
      (node (ref "Q2") (pin "3") (pinfunction "D_3") (pintype "bidirectional"))
    )
    (net (code "39") (name "PWM2") (class "Default")
      (node (ref "Q13") (pin "1") (pinfunction "G_1") (pintype "bidirectional"))
      (node (ref "R30") (pin "1") (pinfunction "1_1") (pintype "passive"))
      (node (ref "U2") (pin "16") (pinfunction "PA6_16") (pintype "bidirectional"))
    )
    (net (code "40") (name "PWM2-OUT") (class "Default")
      (node (ref "C3") (pin "P") (pinfunction "POS_P") (pintype "passive"))
      (node (ref "D3") (pin "C") (pinfunction "C_C") (pintype "passive"))
      (node (ref "JP3") (pin "12V") (pinfunction "2_12V") (pintype "passive"))
      (node (ref "Q3") (pin "3") (pinfunction "D_3") (pintype "bidirectional"))
    )
    (net (code "41") (name "PWM3") (class "Default")
      (node (ref "Q14") (pin "1") (pinfunction "G_1") (pintype "bidirectional"))
      (node (ref "R31") (pin "1") (pinfunction "1_1") (pintype "passive"))
      (node (ref "U2") (pin "18") (pinfunction "PB0_18") (pintype "bidirectional"))
    )
    (net (code "42") (name "PWM3-OUT") (class "Default")
      (node (ref "C4") (pin "P") (pinfunction "POS_P") (pintype "passive"))
      (node (ref "D4") (pin "C") (pinfunction "C_C") (pintype "passive"))
      (node (ref "JP4") (pin "12V") (pinfunction "2_12V") (pintype "passive"))
      (node (ref "Q4") (pin "3") (pinfunction "D_3") (pintype "bidirectional"))
    )
    (net (code "43") (name "PWM4") (class "Default")
      (node (ref "Q15") (pin "1") (pinfunction "G_1") (pintype "bidirectional"))
      (node (ref "R32") (pin "1") (pinfunction "1_1") (pintype "passive"))
      (node (ref "U2") (pin "25") (pinfunction "PB12_25") (pintype "bidirectional"))
    )
    (net (code "44") (name "PWM4-OUT") (class "Default")
      (node (ref "C5") (pin "P") (pinfunction "POS_P") (pintype "passive"))
      (node (ref "D9") (pin "C") (pinfunction "C_C") (pintype "passive"))
      (node (ref "JP5") (pin "12V") (pinfunction "2_12V") (pintype "passive"))
      (node (ref "Q5") (pin "3") (pinfunction "D_3") (pintype "bidirectional"))
    )
    (net (code "45") (name "PWM5") (class "Default")
      (node (ref "Q16") (pin "1") (pinfunction "G_1") (pintype "bidirectional"))
      (node (ref "R33") (pin "1") (pinfunction "1_1") (pintype "passive"))
      (node (ref "U2") (pin "27") (pinfunction "PB14_27") (pintype "bidirectional"))
    )
    (net (code "46") (name "PWM5-OUT") (class "Default")
      (node (ref "C6") (pin "P") (pinfunction "POS_P") (pintype "passive"))
      (node (ref "D10") (pin "C") (pinfunction "C_C") (pintype "passive"))
      (node (ref "JP6") (pin "12V") (pinfunction "2_12V") (pintype "passive"))
      (node (ref "Q6") (pin "3") (pinfunction "D_3") (pintype "bidirectional"))
    )
    (net (code "47") (name "PWM6") (class "Default")
      (node (ref "Q17") (pin "1") (pinfunction "G_1") (pintype "bidirectional"))
      (node (ref "R34") (pin "1") (pinfunction "1_1") (pintype "passive"))
      (node (ref "U2") (pin "42") (pinfunction "PB6_42") (pintype "bidirectional"))
    )
    (net (code "48") (name "PWM6-OUT") (class "Default")
      (node (ref "C7") (pin "P") (pinfunction "POS_P") (pintype "passive"))
      (node (ref "D11") (pin "C") (pinfunction "C_C") (pintype "passive"))
      (node (ref "JP7") (pin "12V") (pinfunction "2_12V") (pintype "passive"))
      (node (ref "Q7") (pin "3") (pinfunction "D_3") (pintype "bidirectional"))
    )
    (net (code "49") (name "PWM7") (class "Default")
      (node (ref "Q18") (pin "1") (pinfunction "G_1") (pintype "bidirectional"))
      (node (ref "R35") (pin "1") (pinfunction "1_1") (pintype "passive"))
      (node (ref "U2") (pin "45") (pinfunction "PB8_45") (pintype "bidirectional"))
    )
    (net (code "50") (name "PWM7-OUT") (class "Default")
      (node (ref "C8") (pin "P") (pinfunction "POS_P") (pintype "passive"))
      (node (ref "D12") (pin "C") (pinfunction "C_C") (pintype "passive"))
      (node (ref "JP8") (pin "12V") (pinfunction "2_12V") (pintype "passive"))
      (node (ref "Q8") (pin "3") (pinfunction "D_3") (pintype "bidirectional"))
    )
    (net (code "51") (name "SCL{slash}TX") (class "Default")
      (node (ref "JP10") (pin "2") (pinfunction "2_2") (pintype "passive"))
      (node (ref "U2") (pin "21") (pinfunction "PB10_21") (pintype "bidirectional"))
    )
    (net (code "52") (name "SDA{slash}RX") (class "Default")
      (node (ref "JP10") (pin "3") (pinfunction "3_3") (pintype "passive"))
      (node (ref "U2") (pin "22") (pinfunction "PB11_22") (pintype "bidirectional"))
    )
    (net (code "53") (name "SWCLK") (class "Default")
      (node (ref "JP9") (pin "2") (pinfunction "2_2") (pintype "passive"))
      (node (ref "U2") (pin "37") (pinfunction "PA14/SWCLK_37") (pintype "bidirectional"))
    )
    (net (code "54") (name "SWDIO") (class "Default")
      (node (ref "JP9") (pin "4") (pinfunction "4_4") (pintype "passive"))
      (node (ref "U2") (pin "34") (pinfunction "PA13/SWDIO_34") (pintype "bidirectional"))
    )
    (net (code "55") (name "SWO") (class "Default")
      (node (ref "JP9") (pin "6") (pinfunction "6_6") (pintype "passive"))
      (node (ref "U2") (pin "39") (pinfunction "PB3/SWO_39") (pintype "bidirectional"))
    )
    (net (code "56") (name "TAC0") (class "Default")
      (node (ref "D5") (pin "1") (pinfunction "A_1") (pintype "bidirectional"))
      (node (ref "R5") (pin "1") (pinfunction "1_1") (pintype "passive"))
      (node (ref "U2") (pin "11") (pinfunction "PA1_11") (pintype "bidirectional"))
    )
    (net (code "57") (name "TAC0-IN") (class "Default")
      (node (ref "D5") (pin "3") (pinfunction "C_3") (pintype "bidirectional"))
      (node (ref "JP1") (pin "TAC") (pinfunction "3_TAC") (pintype "passive"))
    )
    (net (code "58") (name "TAC1") (class "Default")
      (node (ref "D6") (pin "1") (pinfunction "A_1") (pintype "bidirectional"))
      (node (ref "R6") (pin "1") (pinfunction "1_1") (pintype "passive"))
      (node (ref "U2") (pin "13") (pinfunction "PA3_13") (pintype "bidirectional"))
    )
    (net (code "59") (name "TAC1-IN") (class "Default")
      (node (ref "D6") (pin "3") (pinfunction "C_3") (pintype "bidirectional"))
      (node (ref "JP2") (pin "TAC") (pinfunction "3_TAC") (pintype "passive"))
    )
    (net (code "60") (name "TAC2") (class "Default")
      (node (ref "D7") (pin "1") (pinfunction "A_1") (pintype "bidirectional"))
      (node (ref "R7") (pin "1") (pinfunction "1_1") (pintype "passive"))
      (node (ref "U2") (pin "17") (pinfunction "PA7_17") (pintype "bidirectional"))
    )
    (net (code "61") (name "TAC2-IN") (class "Default")
      (node (ref "D7") (pin "3") (pinfunction "C_3") (pintype "bidirectional"))
      (node (ref "JP3") (pin "TAC") (pinfunction "3_TAC") (pintype "passive"))
    )
    (net (code "62") (name "TAC3") (class "Default")
      (node (ref "D8") (pin "1") (pinfunction "A_1") (pintype "bidirectional"))
      (node (ref "R8") (pin "1") (pinfunction "1_1") (pintype "passive"))
      (node (ref "U2") (pin "19") (pinfunction "PB1_19") (pintype "bidirectional"))
    )
    (net (code "63") (name "TAC3-IN") (class "Default")
      (node (ref "D8") (pin "3") (pinfunction "C_3") (pintype "bidirectional"))
      (node (ref "JP4") (pin "TAC") (pinfunction "3_TAC") (pintype "passive"))
    )
    (net (code "64") (name "TAC4") (class "Default")
      (node (ref "D13") (pin "1") (pinfunction "A_1") (pintype "bidirectional"))
      (node (ref "R13") (pin "1") (pinfunction "1_1") (pintype "passive"))
      (node (ref "U2") (pin "26") (pinfunction "PB13_26") (pintype "bidirectional"))
    )
    (net (code "65") (name "TAC4-IN") (class "Default")
      (node (ref "D13") (pin "3") (pinfunction "C_3") (pintype "bidirectional"))
      (node (ref "JP5") (pin "TAC") (pinfunction "3_TAC") (pintype "passive"))
    )
    (net (code "66") (name "TAC5") (class "Default")
      (node (ref "D14") (pin "1") (pinfunction "A_1") (pintype "bidirectional"))
      (node (ref "R14") (pin "1") (pinfunction "1_1") (pintype "passive"))
      (node (ref "U2") (pin "28") (pinfunction "PB15_28") (pintype "bidirectional"))
    )
    (net (code "67") (name "TAC5-IN") (class "Default")
      (node (ref "D14") (pin "3") (pinfunction "C_3") (pintype "bidirectional"))
      (node (ref "JP6") (pin "TAC") (pinfunction "3_TAC") (pintype "passive"))
    )
    (net (code "68") (name "TAC6") (class "Default")
      (node (ref "D15") (pin "1") (pinfunction "A_1") (pintype "bidirectional"))
      (node (ref "R15") (pin "1") (pinfunction "1_1") (pintype "passive"))
      (node (ref "U2") (pin "43") (pinfunction "PB7_43") (pintype "bidirectional"))
    )
    (net (code "69") (name "TAC6-IN") (class "Default")
      (node (ref "D15") (pin "3") (pinfunction "C_3") (pintype "bidirectional"))
      (node (ref "JP7") (pin "TAC") (pinfunction "3_TAC") (pintype "passive"))
    )
    (net (code "70") (name "TAC7") (class "Default")
      (node (ref "D16") (pin "1") (pinfunction "A_1") (pintype "bidirectional"))
      (node (ref "R16") (pin "1") (pinfunction "1_1") (pintype "passive"))
      (node (ref "U2") (pin "46") (pinfunction "PB9_46") (pintype "bidirectional"))
    )
    (net (code "71") (name "TAC7-IN") (class "Default")
      (node (ref "D16") (pin "3") (pinfunction "C_3") (pintype "bidirectional"))
      (node (ref "JP8") (pin "TAC") (pinfunction "3_TAC") (pintype "passive"))
    )
    (net (code "72") (name "USB_N") (class "Default")
      (node (ref "CN1") (pin "DM") (pinfunction "DM_DM") (pintype "passive"))
      (node (ref "U2") (pin "32") (pinfunction "PA11/USBDM_32") (pintype "bidirectional"))
    )
    (net (code "73") (name "USB_P") (class "Default")
      (node (ref "CN1") (pin "DP") (pinfunction "DP_DP") (pintype "passive"))
      (node (ref "R27") (pin "1") (pinfunction "1_1") (pintype "passive"))
      (node (ref "U2") (pin "33") (pinfunction "PA12/USBDP_33") (pintype "bidirectional"))
    )
    (net (code "74") (name "USB_PU") (class "Default")
      (node (ref "R27") (pin "2") (pinfunction "2_2") (pintype "passive"))
      (node (ref "U2") (pin "41") (pinfunction "PB5_41") (pintype "bidirectional"))
    )
    (net (code "75") (name "unconnected-(U2-PC13{slash}TAMPER{slash}RTC-Pad2)") (class "Default")
      (node (ref "U2") (pin "2") (pinfunction "PC13/TAMPER/RTC_2") (pintype "bidirectional"))
    )
    (net (code "76") (name "unconnected-(U2-PC14{slash}OSC32_IN-Pad3)") (class "Default")
      (node (ref "U2") (pin "3") (pinfunction "PC14/OSC32_IN_3") (pintype "bidirectional"))
    )
    (net (code "77") (name "unconnected-(U2-PC15{slash}OSC32_OUT-Pad4)") (class "Default")
      (node (ref "U2") (pin "4") (pinfunction "PC15/OSC32_OUT_4") (pintype "bidirectional"))
    )
  )
)
